# EMB2.net
KiCad netlist of a schematic drawn in EAGLE
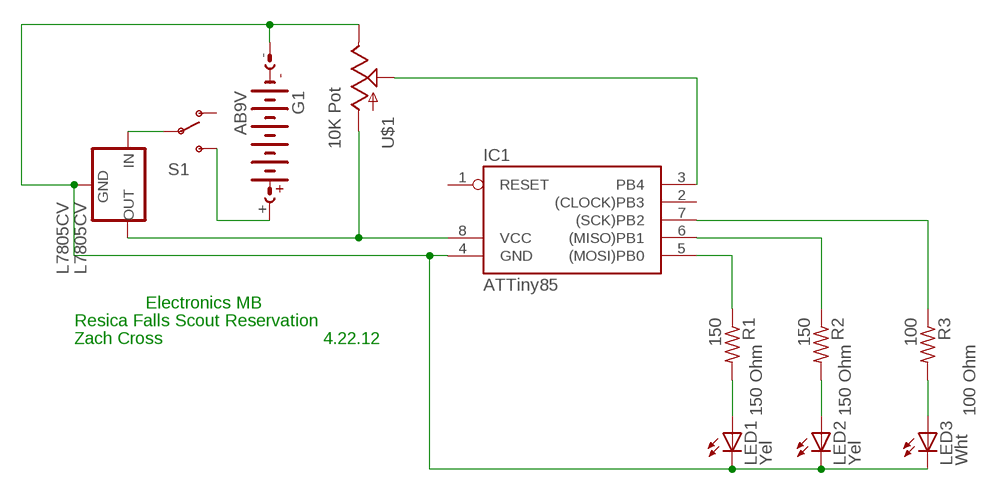
[diagram p0: schematic, sheet 1]

(export (version "E")
  (design (tool "Eeschema 10.0.6"))
  (components
    (comp (ref "G1")
      (value "AB9V")
      (footprint "eagle-import:AB9V")
      (libsource (lib "eagle-import") (part "AB9V"))
    )
    (comp (ref "IC1")
      (value "ATTiny85")
      (footprint "eagle-import:DIL08")
      (libsource (lib "eagle-import") (part "TINY22P"))
    )
    (comp (ref "L7805CV")
      (value "L7805CV")
      (footprint "eagle-import:78XXL")
      (libsource (lib "eagle-import") (part "V_REG_78XXSIDE"))
    )
    (comp (ref "LED1")
      (value "Yel")
      (footprint "eagle-import:LED5MM")
      (fields (field (name "COLOR") "Yellow"))
      (libsource (lib "eagle-import") (part "LED5MM"))
    )
    (comp (ref "LED2")
      (value "Yel")
      (footprint "eagle-import:LED5MM")
      (fields (field (name "COLOR") "Yellow"))
      (libsource (lib "eagle-import") (part "LED5MM"))
    )
    (comp (ref "LED3")
      (value "Wht")
      (footprint "eagle-import:LED5MM")
      (fields (field (name "COLOR") "White"))
      (libsource (lib "eagle-import") (part "LED5MM"))
    )
    (comp (ref "R1")
      (value "150")
      (footprint "eagle-import:0204_7")
      (fields (field (name "RESISTANCE") "150 Ohm"))
      (libsource (lib "eagle-import") (part "R-US_0204/7"))
    )
    (comp (ref "R2")
      (value "150")
      (footprint "eagle-import:0204_7")
      (fields (field (name "RESISTANCE") "150 Ohm"))
      (libsource (lib "eagle-import") (part "R-US_0204/7"))
    )
    (comp (ref "R3")
      (value "100")
      (footprint "eagle-import:0204_7")
      (fields (field (name "RESISTANCE") "100 Ohm"))
      (libsource (lib "eagle-import") (part "R-US_0204/7"))
    )
    (comp (ref "S1")
      (value "SWITCH-SPSTPTH")
      (footprint "eagle-import:SWITCH-SPDT")
      (libsource (lib "eagle-import") (part "SWITCH-SPSTPTH"))
    )
    (comp (ref "U$1")
      (value "10K Pot")
      (footprint "eagle-import:ALPS_POT")
      (libsource (lib "eagle-import") (part "POT"))
    )
  )
  (nets
    (net (code "1") (name "Net-(IC1-(MISO)PB1)") (class "Default")
      (node (ref "IC1") (pin "6") (pinfunction "(MISO)PB1_6") (pintype "bidirectional"))
      (node (ref "R2") (pin "1") (pinfunction "1_1") (pintype "passive"))
    )
    (net (code "2") (name "Net-(IC1-(MOSI)PB0)") (class "Default")
      (node (ref "IC1") (pin "5") (pinfunction "(MOSI)PB0_5") (pintype "bidirectional"))
      (node (ref "R1") (pin "1") (pinfunction "1_1") (pintype "passive"))
    )
    (net (code "3") (name "Net-(IC1-(SCK)PB2)") (class "Default")
      (node (ref "IC1") (pin "7") (pinfunction "(SCK)PB2_7") (pintype "bidirectional"))
      (node (ref "R3") (pin "1") (pinfunction "1_1") (pintype "passive"))
    )
    (net (code "4") (name "Net-(IC1-GND)") (class "Default")
      (node (ref "G1") (pin "-") (pinfunction "-_-") (pintype "passive"))
      (node (ref "IC1") (pin "4") (pinfunction "GND_4") (pintype "power_in"))
      (node (ref "L7805CV") (pin "GND") (pinfunction "GND_GND") (pintype "input"))
      (node (ref "LED1") (pin "K") (pinfunction "C_K") (pintype "passive"))
      (node (ref "LED2") (pin "K") (pinfunction "C_K") (pintype "passive"))
      (node (ref "LED3") (pin "K") (pinfunction "C_K") (pintype "passive"))
      (node (ref "U$1") (pin "P$1") (pinfunction "E_P$1") (pintype "passive"))
    )
    (net (code "5") (name "Net-(IC1-PB4)") (class "Default")
      (node (ref "IC1") (pin "3") (pinfunction "PB4_3") (pintype "bidirectional"))
      (node (ref "U$1") (pin "P$2") (pinfunction "S_P$2") (pintype "passive"))
    )
    (net (code "6") (name "Net-(IC1-VCC)") (class "Default")
      (node (ref "IC1") (pin "8") (pinfunction "VCC_8") (pintype "power_in"))
      (node (ref "L7805CV") (pin "OUT") (pinfunction "OUT_OUT") (pintype "output"))
      (node (ref "U$1") (pin "P$3") (pinfunction "A_P$3") (pintype "passive"))
    )
    (net (code "7") (name "Net-(LED1-PadA)") (class "Default")
      (node (ref "LED1") (pin "A") (pinfunction "A_A") (pintype "passive"))
      (node (ref "R1") (pin "2") (pinfunction "2_2") (pintype "passive"))
    )
    (net (code "8") (name "Net-(LED2-PadA)") (class "Default")
      (node (ref "LED2") (pin "A") (pinfunction "A_A") (pintype "passive"))
      (node (ref "R2") (pin "2") (pinfunction "2_2") (pintype "passive"))
    )
    (net (code "9") (name "Net-(LED3-PadA)") (class "Default")
      (node (ref "LED3") (pin "A") (pinfunction "A_A") (pintype "passive"))
      (node (ref "R3") (pin "2") (pinfunction "2_2") (pintype "passive"))
    )
    (net (code "10") (name "Net-(S1-P)") (class "Default")
      (node (ref "L7805CV") (pin "IN") (pinfunction "IN_IN") (pintype "input"))
      (node (ref "S1") (pin "2") (pinfunction "P_2") (pintype "passive"))
    )
    (net (code "11") (name "Net-(S1-S)") (class "Default")
      (node (ref "G1") (pin "+") (pinfunction "+_+") (pintype "passive"))
      (node (ref "S1") (pin "3") (pinfunction "S_3") (pintype "passive"))
    )
    (net (code "12") (name "unconnected-(IC1-(CLOCK)PB3-Pad2)") (class "Default")
      (node (ref "IC1") (pin "2") (pinfunction "(CLOCK)PB3_2") (pintype "bidirectional"))
    )
    (net (code "13") (name "unconnected-(IC1-RESET-Pad1)") (class "Default")
      (node (ref "IC1") (pin "1") (pinfunction "RESET_1") (pintype "input"))
    )
    (net (code "14") (name "unconnected-(S1-O-Pad1)") (class "Default")
      (node (ref "S1") (pin "1") (pinfunction "O_1") (pintype "passive"))
    )
  )
)
